# PulseFit-Bottom.net
KiCad netlist of a schematic drawn in EAGLE
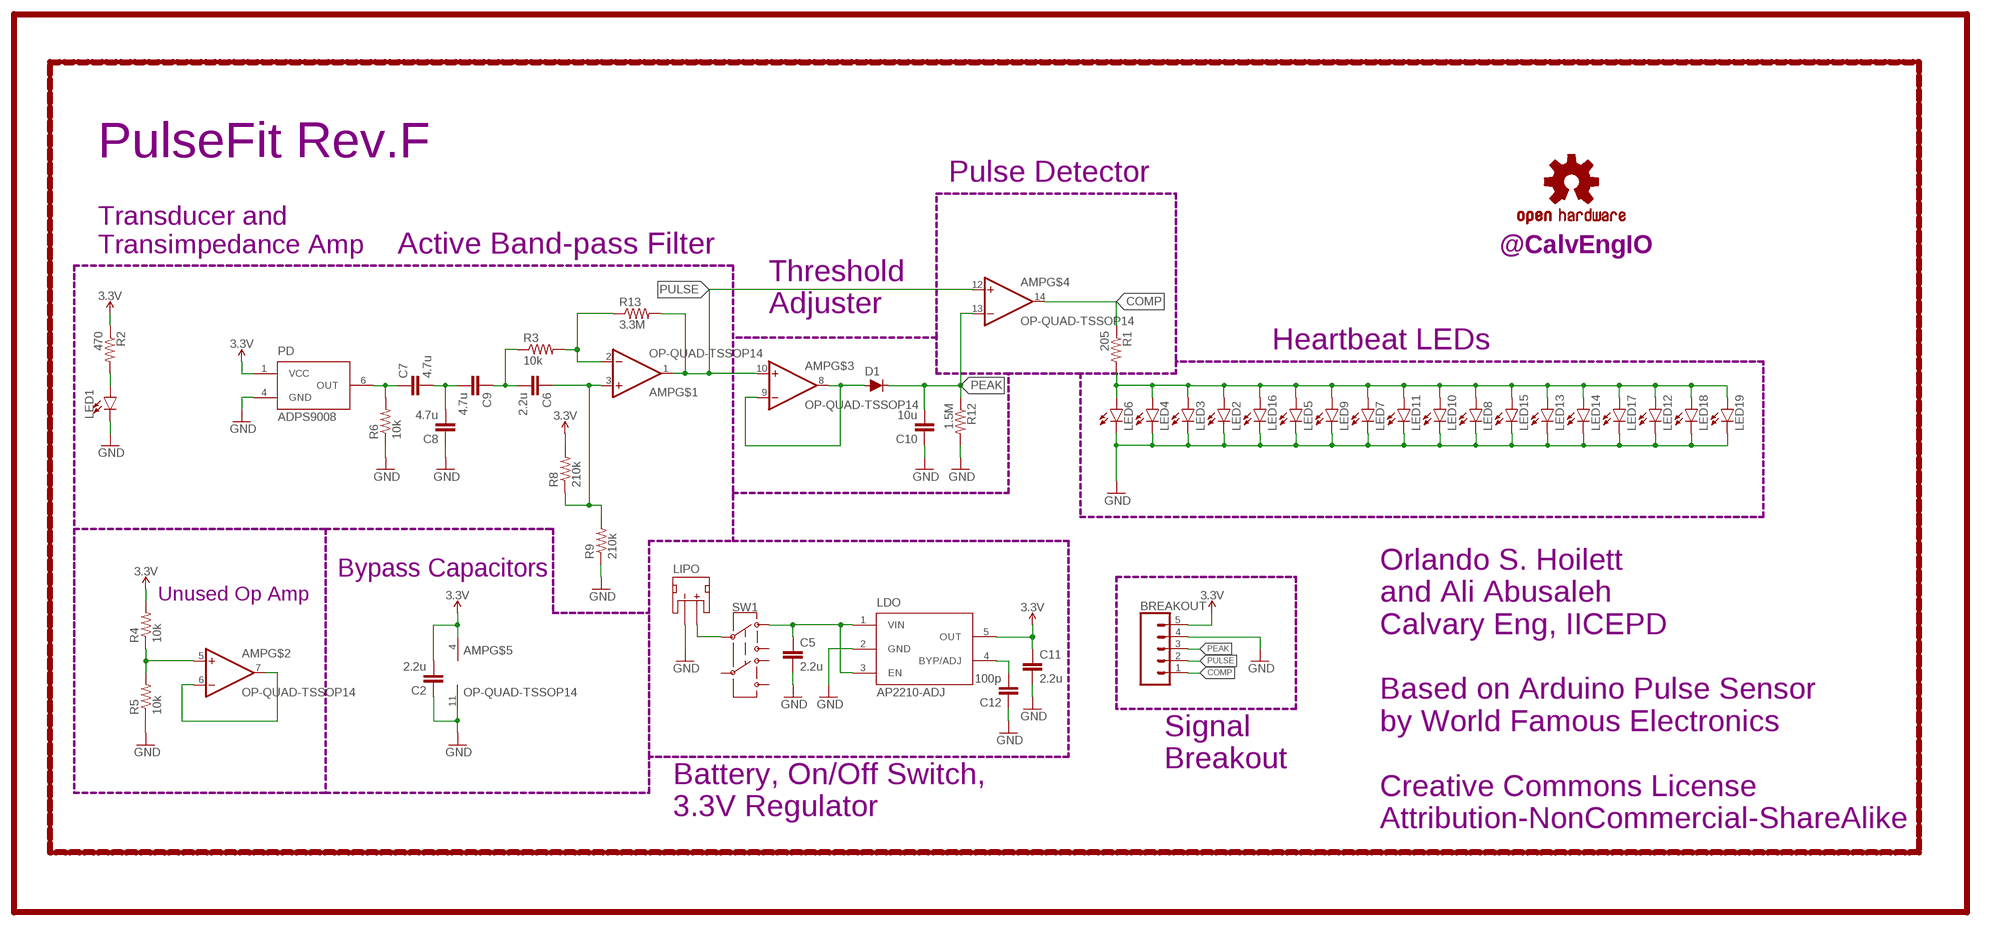
[diagram p0: schematic, sheet 1]

(export (version "E")
  (design (tool "Eeschema 10.0.6"))
  (components
    (comp (ref "AMP")
      (value "OP-QUAD-TSSOP14")
      (footprint "eagle-import:TSSOP14")
      (libsource (lib "eagle-import") (part "OP-QUAD-TSSOP14"))
    )
    (comp (ref "BREAKOUT")
      (value "CONN_05NO_SILK")
      (footprint "eagle-import:1X05_NO_SILK")
      (libsource (lib "eagle-import") (part "CONN_05NO_SILK"))
    )
    (comp (ref "C2")
      (value "2.2u")
      (footprint "eagle-import:C0402")
      (libsource (lib "eagle-import") (part "CAPACITOR0402"))
    )
    (comp (ref "C5")
      (value "2.2u")
      (footprint "eagle-import:C0603")
      (libsource (lib "eagle-import") (part "CAPACITOR0603"))
    )
    (comp (ref "C6")
      (value "2.2u")
      (footprint "eagle-import:C0603")
      (libsource (lib "eagle-import") (part "CAPACITOR0603"))
    )
    (comp (ref "C7")
      (value "4.7u")
      (footprint "eagle-import:C0603")
      (libsource (lib "eagle-import") (part "CAPACITOR0603"))
    )
    (comp (ref "C8")
      (value "4.7u")
      (footprint "eagle-import:C0603")
      (libsource (lib "eagle-import") (part "CAPACITOR0603"))
    )
    (comp (ref "C9")
      (value "4.7u")
      (footprint "eagle-import:C0603")
      (libsource (lib "eagle-import") (part "CAPACITOR0603"))
    )
    (comp (ref "C10")
      (value "10u")
      (footprint "eagle-import:C0805")
      (libsource (lib "eagle-import") (part "CAPACITOR0805"))
    )
    (comp (ref "C11")
      (value "2.2u")
      (footprint "eagle-import:C0603")
      (libsource (lib "eagle-import") (part "CAPACITOR0603"))
    )
    (comp (ref "C12")
      (value "100p")
      (footprint "eagle-import:C0402")
      (libsource (lib "eagle-import") (part "CAPACITOR0402"))
    )
    (comp (ref "D1")
      (value "DIODE-BAS16J")
      (footprint "eagle-import:SOD-323")
      (libsource (lib "eagle-import") (part "DIODE-BAS16J"))
    )
    (comp (ref "LDO")
      (value "AP2210-ADJ")
      (footprint "eagle-import:SOT23-5")
      (libsource (lib "eagle-import") (part "AP2210-ADJ"))
    )
    (comp (ref "LED1")
      (value "LEDZ-BEND")
      (footprint "eagle-import:2-SMD.Z-BEND")
      (libsource (lib "eagle-import") (part "LEDZ-BEND"))
    )
    (comp (ref "LED2")
      (value "LED5MM")
      (footprint "eagle-import:LED5MM")
      (libsource (lib "eagle-import") (part "SparkFun-LED_LED5MM"))
    )
    (comp (ref "LED3")
      (value "LED5MM")
      (footprint "eagle-import:LED5MM")
      (libsource (lib "eagle-import") (part "SparkFun-LED_LED5MM"))
    )
    (comp (ref "LED4")
      (value "LED5MM")
      (footprint "eagle-import:LED5MM")
      (libsource (lib "eagle-import") (part "SparkFun-LED_LED5MM"))
    )
    (comp (ref "LED5")
      (value "LED5MM")
      (footprint "eagle-import:LED5MM")
      (libsource (lib "eagle-import") (part "SparkFun-LED_LED5MM"))
    )
    (comp (ref "LED6")
      (value "LED5MM")
      (footprint "eagle-import:LED5MM")
      (libsource (lib "eagle-import") (part "SparkFun-LED_LED5MM"))
    )
    (comp (ref "LED7")
      (value "LED5MM")
      (footprint "eagle-import:LED5MM")
      (libsource (lib "eagle-import") (part "SparkFun-LED_LED5MM"))
    )
    (comp (ref "LED8")
      (value "LED5MM")
      (footprint "eagle-import:LED5MM")
      (libsource (lib "eagle-import") (part "SparkFun-LED_LED5MM"))
    )
    (comp (ref "LED9")
      (value "LED5MM")
      (footprint "eagle-import:LED5MM")
      (libsource (lib "eagle-import") (part "SparkFun-LED_LED5MM"))
    )
    (comp (ref "LED10")
      (value "LED5MM")
      (footprint "eagle-import:LED5MM")
      (libsource (lib "eagle-import") (part "SparkFun-LED_LED5MM"))
    )
    (comp (ref "LED11")
      (value "LED5MM")
      (footprint "eagle-import:LED5MM")
      (libsource (lib "eagle-import") (part "SparkFun-LED_LED5MM"))
    )
    (comp (ref "LED12")
      (value "LED5MM")
      (footprint "eagle-import:LED5MM")
      (libsource (lib "eagle-import") (part "SparkFun-LED_LED5MM"))
    )
    (comp (ref "LED13")
      (value "LED5MM")
      (footprint "eagle-import:LED5MM")
      (libsource (lib "eagle-import") (part "SparkFun-LED_LED5MM"))
    )
    (comp (ref "LED14")
      (value "LED5MM")
      (footprint "eagle-import:LED5MM")
      (libsource (lib "eagle-import") (part "SparkFun-LED_LED5MM"))
    )
    (comp (ref "LED15")
      (value "LED5MM")
      (footprint "eagle-import:LED5MM")
      (libsource (lib "eagle-import") (part "SparkFun-LED_LED5MM"))
    )
    (comp (ref "LED16")
      (value "LED5MM")
      (footprint "eagle-import:LED5MM")
      (libsource (lib "eagle-import") (part "SparkFun-LED_LED5MM"))
    )
    (comp (ref "LED17")
      (value "LED5MM")
      (footprint "eagle-import:LED5MM")
      (libsource (lib "eagle-import") (part "SparkFun-LED_LED5MM"))
    )
    (comp (ref "LED18")
      (value "LED5MM")
      (footprint "eagle-import:LED5MM")
      (libsource (lib "eagle-import") (part "SparkFun-LED_LED5MM"))
    )
    (comp (ref "LED19")
      (value "LED5MM")
      (footprint "eagle-import:LED5MM")
      (libsource (lib "eagle-import") (part "SparkFun-LED_LED5MM"))
    )
    (comp (ref "LIPO")
      (value "JST_2MM_MALE")
      (footprint "eagle-import:JST-2-SMD")
      (libsource (lib "eagle-import") (part "JST_2MM_MALE"))
    )
    (comp (ref "LOGO1")
      (value "OSHW-LOGOS")
      (footprint "eagle-import:OSHW-LOGO-S")
      (libsource (lib "eagle-import") (part "OSHW-LOGOS"))
    )
    (comp (ref "PD")
      (value "ADPS9008")
      (footprint "eagle-import:6-PIN.CHIPLED")
      (libsource (lib "eagle-import") (part "ADPS9008"))
    )
    (comp (ref "R1")
      (value "205")
      (footprint "eagle-import:R0402")
      (libsource (lib "eagle-import") (part "RESISTOR0402"))
    )
    (comp (ref "R2")
      (value "470")
      (footprint "eagle-import:R0402")
      (libsource (lib "eagle-import") (part "RESISTOR0402"))
    )
    (comp (ref "R3")
      (value "10k")
      (footprint "eagle-import:R0402")
      (libsource (lib "eagle-import") (part "RESISTOR0402"))
    )
    (comp (ref "R4")
      (value "10k")
      (footprint "eagle-import:R0402")
      (libsource (lib "eagle-import") (part "RESISTOR0402"))
    )
    (comp (ref "R5")
      (value "10k")
      (footprint "eagle-import:R0402")
      (libsource (lib "eagle-import") (part "RESISTOR0402"))
    )
    (comp (ref "R6")
      (value "10k")
      (footprint "eagle-import:R0402")
      (libsource (lib "eagle-import") (part "RESISTOR0402"))
    )
    (comp (ref "R8")
      (value "210k")
      (footprint "eagle-import:R0402")
      (libsource (lib "eagle-import") (part "RESISTOR0402"))
    )
    (comp (ref "R9")
      (value "210k")
      (footprint "eagle-import:R0402")
      (libsource (lib "eagle-import") (part "RESISTOR0402"))
    )
    (comp (ref "R12")
      (value "1.5M")
      (footprint "eagle-import:R0402")
      (libsource (lib "eagle-import") (part "RESISTOR0402"))
    )
    (comp (ref "R13")
      (value "3.3M")
      (footprint "eagle-import:R0402")
      (libsource (lib "eagle-import") (part "RESISTOR0402"))
    )
    (comp (ref "SW1")
      (value "SWITCH.JS202011JCQN")
      (footprint "eagle-import:SWITCH.00")
      (libsource (lib "eagle-import") (part "SWITCH.JS202011JCQN"))
    )
    (comp (ref "U$1")
      (value "CALVENGIO_HANDLEHANDLE.05")
      (footprint "eagle-import:CALVENGIO_HANDLE.05")
      (libsource (lib "eagle-import") (part "CALVENGIO_HANDLEHANDLE.05"))
    )
  )
  (nets
    (net (code "1") (name "3.3V") (class "Default")
      (node (ref "AMP") (pin "4") (pinfunction "V+_4") (pintype "power_in"))
      (node (ref "BREAKOUT") (pin "5") (pinfunction "5_5") (pintype "passive"))
      (node (ref "C11") (pin "1") (pinfunction "1_1") (pintype "passive"))
      (node (ref "C2") (pin "2") (pinfunction "2_2") (pintype "passive"))
      (node (ref "LDO") (pin "5") (pinfunction "OUT_5") (pintype "bidirectional"))
      (node (ref "PD") (pin "1") (pinfunction "VCC_1") (pintype "bidirectional"))
      (node (ref "R2") (pin "1") (pinfunction "1_1") (pintype "passive"))
      (node (ref "R4") (pin "2") (pinfunction "2_2") (pintype "passive"))
      (node (ref "R8") (pin "2") (pinfunction "2_2") (pintype "passive"))
    )
    (net (code "2") (name "COMP") (class "Default")
      (node (ref "AMP") (pin "14") (pinfunction "OUT_14") (pintype "output"))
      (node (ref "BREAKOUT") (pin "1") (pinfunction "1_1") (pintype "passive"))
      (node (ref "R1") (pin "1") (pinfunction "1_1") (pintype "passive"))
    )
    (net (code "3") (name "GND") (class "Default")
      (node (ref "AMP") (pin "11") (pinfunction "V-_11") (pintype "power_in"))
      (node (ref "BREAKOUT") (pin "4") (pinfunction "4_4") (pintype "passive"))
      (node (ref "C10") (pin "1") (pinfunction "1_1") (pintype "passive"))
      (node (ref "C11") (pin "2") (pinfunction "2_2") (pintype "passive"))
      (node (ref "C12") (pin "1") (pinfunction "1_1") (pintype "passive"))
      (node (ref "C2") (pin "1") (pinfunction "1_1") (pintype "passive"))
      (node (ref "C5") (pin "2") (pinfunction "2_2") (pintype "passive"))
      (node (ref "C8") (pin "1") (pinfunction "1_1") (pintype "passive"))
      (node (ref "LDO") (pin "2") (pinfunction "GND_2") (pintype "bidirectional"))
      (node (ref "LED1") (pin "-") (pinfunction "C_-") (pintype "passive"))
      (node (ref "LED10") (pin "K") (pinfunction "C_K") (pintype "passive"))
      (node (ref "LED11") (pin "K") (pinfunction "C_K") (pintype "passive"))
      (node (ref "LED12") (pin "K") (pinfunction "C_K") (pintype "passive"))
      (node (ref "LED13") (pin "K") (pinfunction "C_K") (pintype "passive"))
      (node (ref "LED14") (pin "K") (pinfunction "C_K") (pintype "passive"))
      (node (ref "LED15") (pin "K") (pinfunction "C_K") (pintype "passive"))
      (node (ref "LED16") (pin "K") (pinfunction "C_K") (pintype "passive"))
      (node (ref "LED17") (pin "K") (pinfunction "C_K") (pintype "passive"))
      (node (ref "LED18") (pin "K") (pinfunction "C_K") (pintype "passive"))
      (node (ref "LED19") (pin "K") (pinfunction "C_K") (pintype "passive"))
      (node (ref "LED2") (pin "K") (pinfunction "C_K") (pintype "passive"))
      (node (ref "LED3") (pin "K") (pinfunction "C_K") (pintype "passive"))
      (node (ref "LED4") (pin "K") (pinfunction "C_K") (pintype "passive"))
      (node (ref "LED5") (pin "K") (pinfunction "C_K") (pintype "passive"))
      (node (ref "LED6") (pin "K") (pinfunction "C_K") (pintype "passive"))
      (node (ref "LED7") (pin "K") (pinfunction "C_K") (pintype "passive"))
      (node (ref "LED8") (pin "K") (pinfunction "C_K") (pintype "passive"))
      (node (ref "LED9") (pin "K") (pinfunction "C_K") (pintype "passive"))
      (node (ref "LIPO") (pin "1") (pinfunction "-_1") (pintype "bidirectional"))
      (node (ref "PD") (pin "4") (pinfunction "GND_4") (pintype "bidirectional"))
      (node (ref "R12") (pin "2") (pinfunction "2_2") (pintype "passive"))
      (node (ref "R5") (pin "1") (pinfunction "1_1") (pintype "passive"))
      (node (ref "R6") (pin "1") (pinfunction "1_1") (pintype "passive"))
      (node (ref "R9") (pin "1") (pinfunction "1_1") (pintype "passive"))
    )
    (net (code "4") (name "Net-(AMPA-+IN)") (class "Default")
      (node (ref "AMP") (pin "3") (pinfunction "+IN_3") (pintype "input"))
      (node (ref "C6") (pin "1") (pinfunction "1_1") (pintype "passive"))
      (node (ref "R8") (pin "1") (pinfunction "1_1") (pintype "passive"))
      (node (ref "R9") (pin "2") (pinfunction "2_2") (pintype "passive"))
    )
    (net (code "5") (name "Net-(AMPA--IN)") (class "Default")
      (node (ref "AMP") (pin "2") (pinfunction "-IN_2") (pintype "input"))
      (node (ref "R13") (pin "1") (pinfunction "1_1") (pintype "passive"))
      (node (ref "R3") (pin "2") (pinfunction "2_2") (pintype "passive"))
    )
    (net (code "6") (name "Net-(AMPB-+IN)") (class "Default")
      (node (ref "AMP") (pin "5") (pinfunction "+IN_5") (pintype "input"))
      (node (ref "R4") (pin "1") (pinfunction "1_1") (pintype "passive"))
      (node (ref "R5") (pin "2") (pinfunction "2_2") (pintype "passive"))
    )
    (net (code "7") (name "Net-(AMPB--IN)") (class "Default")
      (node (ref "AMP") (pin "6") (pinfunction "-IN_6") (pintype "input"))
      (node (ref "AMP") (pin "7") (pinfunction "OUT_7") (pintype "output"))
    )
    (net (code "8") (name "Net-(AMPC--IN)") (class "Default")
      (node (ref "AMP") (pin "8") (pinfunction "OUT_8") (pintype "output"))
      (node (ref "AMP") (pin "9") (pinfunction "-IN_9") (pintype "input"))
      (node (ref "D1") (pin "A") (pinfunction "A_A") (pintype "passive"))
    )
    (net (code "9") (name "Net-(C6-Pad2)") (class "Default")
      (node (ref "C6") (pin "2") (pinfunction "2_2") (pintype "passive"))
      (node (ref "C9") (pin "1") (pinfunction "1_1") (pintype "passive"))
      (node (ref "R3") (pin "1") (pinfunction "1_1") (pintype "passive"))
    )
    (net (code "10") (name "Net-(C7-Pad2)") (class "Default")
      (node (ref "C7") (pin "2") (pinfunction "2_2") (pintype "passive"))
      (node (ref "C8") (pin "2") (pinfunction "2_2") (pintype "passive"))
      (node (ref "C9") (pin "2") (pinfunction "2_2") (pintype "passive"))
    )
    (net (code "11") (name "Net-(LDO-BYP{slash}ADJ)") (class "Default")
      (node (ref "C12") (pin "2") (pinfunction "2_2") (pintype "passive"))
      (node (ref "LDO") (pin "4") (pinfunction "BYP/ADJ_4") (pintype "bidirectional"))
    )
    (net (code "12") (name "Net-(LDO-EN)") (class "Default")
      (node (ref "C5") (pin "1") (pinfunction "1_1") (pintype "passive"))
      (node (ref "LDO") (pin "1") (pinfunction "VIN_1") (pintype "bidirectional"))
      (node (ref "LDO") (pin "3") (pinfunction "EN_3") (pintype "bidirectional"))
      (node (ref "SW1") (pin "1") (pinfunction "1_1") (pintype "bidirectional"))
    )
    (net (code "13") (name "Net-(LED1-A)") (class "Default")
      (node (ref "LED1") (pin "+") (pinfunction "A_+") (pintype "passive"))
      (node (ref "R2") (pin "2") (pinfunction "2_2") (pintype "passive"))
    )
    (net (code "14") (name "Net-(LED10-PadA)") (class "Default")
      (node (ref "LED10") (pin "A") (pinfunction "A_A") (pintype "passive"))
      (node (ref "LED11") (pin "A") (pinfunction "A_A") (pintype "passive"))
      (node (ref "LED12") (pin "A") (pinfunction "A_A") (pintype "passive"))
      (node (ref "LED13") (pin "A") (pinfunction "A_A") (pintype "passive"))
      (node (ref "LED14") (pin "A") (pinfunction "A_A") (pintype "passive"))
      (node (ref "LED15") (pin "A") (pinfunction "A_A") (pintype "passive"))
      (node (ref "LED16") (pin "A") (pinfunction "A_A") (pintype "passive"))
      (node (ref "LED17") (pin "A") (pinfunction "A_A") (pintype "passive"))
      (node (ref "LED18") (pin "A") (pinfunction "A_A") (pintype "passive"))
      (node (ref "LED19") (pin "A") (pinfunction "A_A") (pintype "passive"))
      (node (ref "LED2") (pin "A") (pinfunction "A_A") (pintype "passive"))
      (node (ref "LED3") (pin "A") (pinfunction "A_A") (pintype "passive"))
      (node (ref "LED4") (pin "A") (pinfunction "A_A") (pintype "passive"))
      (node (ref "LED5") (pin "A") (pinfunction "A_A") (pintype "passive"))
      (node (ref "LED6") (pin "A") (pinfunction "A_A") (pintype "passive"))
      (node (ref "LED7") (pin "A") (pinfunction "A_A") (pintype "passive"))
      (node (ref "LED8") (pin "A") (pinfunction "A_A") (pintype "passive"))
      (node (ref "LED9") (pin "A") (pinfunction "A_A") (pintype "passive"))
      (node (ref "R1") (pin "2") (pinfunction "2_2") (pintype "passive"))
    )
    (net (code "15") (name "Net-(LIPO-+)") (class "Default")
      (node (ref "LIPO") (pin "2") (pinfunction "+_2") (pintype "bidirectional"))
      (node (ref "SW1") (pin "2") (pinfunction "2_2") (pintype "bidirectional"))
    )
    (net (code "16") (name "Net-(PD-OUT)") (class "Default")
      (node (ref "C7") (pin "1") (pinfunction "1_1") (pintype "passive"))
      (node (ref "PD") (pin "6") (pinfunction "OUT_6") (pintype "bidirectional"))
      (node (ref "R6") (pin "2") (pinfunction "2_2") (pintype "passive"))
    )
    (net (code "17") (name "PEAK") (class "Default")
      (node (ref "AMP") (pin "13") (pinfunction "-IN_13") (pintype "input"))
      (node (ref "BREAKOUT") (pin "3") (pinfunction "3_3") (pintype "passive"))
      (node (ref "C10") (pin "2") (pinfunction "2_2") (pintype "passive"))
      (node (ref "D1") (pin "C") (pinfunction "C_C") (pintype "passive"))
      (node (ref "R12") (pin "1") (pinfunction "1_1") (pintype "passive"))
    )
    (net (code "18") (name "PULSE") (class "Default")
      (node (ref "AMP") (pin "1") (pinfunction "OUT_1") (pintype "output"))
      (node (ref "AMP") (pin "10") (pinfunction "+IN_10") (pintype "input"))
      (node (ref "AMP") (pin "12") (pinfunction "+IN_12") (pintype "input"))
      (node (ref "BREAKOUT") (pin "2") (pinfunction "2_2") (pintype "passive"))
      (node (ref "R13") (pin "2") (pinfunction "2_2") (pintype "passive"))
    )
    (net (code "19") (name "unconnected-(LIPO-PAD1-PadNC1)") (class "Default")
      (node (ref "LIPO") (pin "NC1") (pinfunction "PAD1_NC1") (pintype "bidirectional"))
    )
    (net (code "20") (name "unconnected-(LIPO-PAD2-PadNC2)") (class "Default")
      (node (ref "LIPO") (pin "NC2") (pinfunction "PAD2_NC2") (pintype "bidirectional"))
    )
    (net (code "21") (name "unconnected-(SW1-Pad3)") (class "Default")
      (node (ref "SW1") (pin "3") (pinfunction "3_3") (pintype "bidirectional"))
    )
    (net (code "22") (name "unconnected-(SW1-Pad5)") (class "Default")
      (node (ref "SW1") (pin "5") (pinfunction "5_5") (pintype "bidirectional"))
    )
    (net (code "23") (name "unconnected-(SW1-Pad6)") (class "Default")
      (node (ref "SW1") (pin "6") (pinfunction "6_6") (pintype "bidirectional"))
    )
    (net (code "24") (name "unconnected-(SW1-Pad7)") (class "Default")
      (node (ref "SW1") (pin "7") (pinfunction "7_7") (pintype "bidirectional"))
    )
  )
)
